# goodfet42jtag.net
KiCad netlist of a schematic drawn in EAGLE
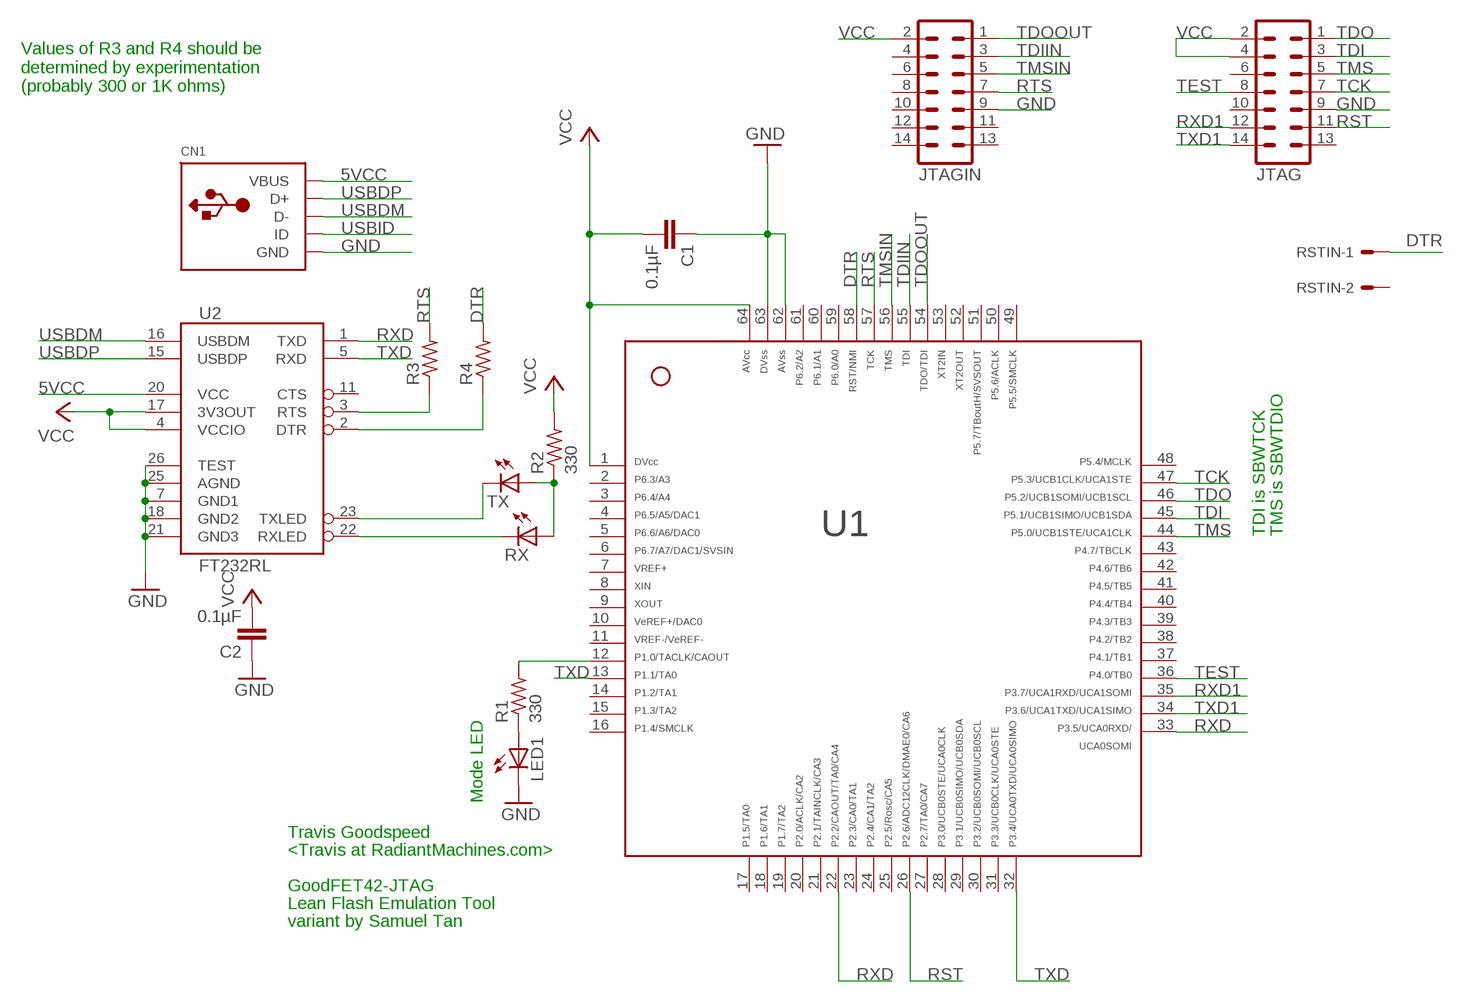
[diagram p0: schematic, sheet 1]

(export (version "E")
  (design (tool "Eeschema 10.0.6"))
  (components
    (comp (ref "C1")
      (value "0.1µF")
      (footprint "eagle-import:C0603")
      (libsource (lib "eagle-import") (part "C-EUC0603"))
    )
    (comp (ref "C2")
      (value "0.1µF")
      (footprint "eagle-import:C0603")
      (libsource (lib "eagle-import") (part "C-EUC0603"))
    )
    (comp (ref "CN1")
      (value "USBMINIB")
      (footprint "eagle-import:USB-MINIB")
      (libsource (lib "eagle-import") (part "USBMINIB"))
    )
    (comp (ref "JTAG")
      (value "MA07-2")
      (footprint "eagle-import:MA07-2")
      (libsource (lib "eagle-import") (part "MA07-2"))
    )
    (comp (ref "JTAGIN")
      (value "MA07-2")
      (footprint "eagle-import:MA07-2")
      (libsource (lib "eagle-import") (part "MA07-2"))
    )
    (comp (ref "LED1")
      (value "LEDCHIP-LED0603")
      (footprint "eagle-import:CHIP-LED0603")
      (libsource (lib "eagle-import") (part "LEDCHIP-LED0603"))
    )
    (comp (ref "R1")
      (value "330")
      (footprint "eagle-import:R0603")
      (libsource (lib "eagle-import") (part "R-US_R0603"))
    )
    (comp (ref "R2")
      (value "330")
      (footprint "eagle-import:R0603")
      (libsource (lib "eagle-import") (part "R-US_R0603"))
    )
    (comp (ref "R3")
      (value "R-US_R0603")
      (footprint "eagle-import:R0603")
      (libsource (lib "eagle-import") (part "R-US_R0603"))
    )
    (comp (ref "R4")
      (value "R-US_R0603")
      (footprint "eagle-import:R0603")
      (libsource (lib "eagle-import") (part "R-US_R0603"))
    )
    (comp (ref "RSTIN")
      (value "332-02")
      (footprint "eagle-import:332-02")
      (libsource (lib "eagle-import") (part "332-02"))
    )
    (comp (ref "RX")
      (value "LEDCHIP-LED0603")
      (footprint "eagle-import:CHIP-LED0603")
      (libsource (lib "eagle-import") (part "LEDCHIP-LED0603"))
    )
    (comp (ref "TX")
      (value "LEDCHIP-LED0603")
      (footprint "eagle-import:CHIP-LED0603")
      (libsource (lib "eagle-import") (part "LEDCHIP-LED0603"))
    )
    (comp (ref "U1")
      (value "MSP430F2618TPM")
      (footprint "eagle-import:PM_PAG64")
      (libsource (lib "eagle-import") (part "F261X---PM64"))
    )
    (comp (ref "U2")
      (value "FT232RL")
      (footprint "eagle-import:SSOP28DB")
      (libsource (lib "eagle-import") (part "FT232RL-BASICSSOP"))
    )
  )
  (nets
    (net (code "1") (name "/5VCC") (class "Default")
      (node (ref "CN1") (pin "VBUS") (pinfunction "VBUS_VBUS") (pintype "power_in"))
      (node (ref "U2") (pin "20") (pinfunction "VCC_20") (pintype "power_in"))
    )
    (net (code "2") (name "/DTR") (class "Default")
      (node (ref "R4") (pin "2") (pinfunction "2_2") (pintype "passive"))
      (node (ref "RSTIN") (pin "1") (pinfunction "S_1") (pintype "passive"))
      (node (ref "U1") (pin "58") (pinfunction "58_58") (pintype "input"))
    )
    (net (code "3") (name "/RST") (class "Default")
      (node (ref "JTAG") (pin "11") (pinfunction "11_11") (pintype "passive"))
      (node (ref "U1") (pin "26") (pinfunction "26_26") (pintype "bidirectional"))
    )
    (net (code "4") (name "/RTS") (class "Default")
      (node (ref "JTAGIN") (pin "7") (pinfunction "7_7") (pintype "passive"))
      (node (ref "R3") (pin "2") (pinfunction "2_2") (pintype "passive"))
      (node (ref "U1") (pin "57") (pinfunction "57_57") (pintype "input"))
    )
    (net (code "5") (name "/RXD") (class "Default")
      (node (ref "U1") (pin "22") (pinfunction "22_22") (pintype "bidirectional"))
      (node (ref "U1") (pin "33") (pinfunction "33_33") (pintype "bidirectional"))
      (node (ref "U2") (pin "1") (pinfunction "TXD_1") (pintype "output"))
    )
    (net (code "6") (name "/RXD1") (class "Default")
      (node (ref "JTAG") (pin "12") (pinfunction "12_12") (pintype "passive"))
      (node (ref "U1") (pin "35") (pinfunction "35_35") (pintype "bidirectional"))
    )
    (net (code "7") (name "/TCK") (class "Default")
      (node (ref "JTAG") (pin "7") (pinfunction "7_7") (pintype "passive"))
      (node (ref "U1") (pin "47") (pinfunction "47_47") (pintype "bidirectional"))
    )
    (net (code "8") (name "/TDI") (class "Default")
      (node (ref "JTAG") (pin "3") (pinfunction "3_3") (pintype "passive"))
      (node (ref "U1") (pin "45") (pinfunction "45_45") (pintype "bidirectional"))
    )
    (net (code "9") (name "/TDIIN") (class "Default")
      (node (ref "JTAGIN") (pin "3") (pinfunction "3_3") (pintype "passive"))
      (node (ref "U1") (pin "55") (pinfunction "55_55") (pintype "input"))
    )
    (net (code "10") (name "/TDO") (class "Default")
      (node (ref "JTAG") (pin "1") (pinfunction "1_1") (pintype "passive"))
      (node (ref "U1") (pin "46") (pinfunction "46_46") (pintype "bidirectional"))
    )
    (net (code "11") (name "/TDOOUT") (class "Default")
      (node (ref "JTAGIN") (pin "1") (pinfunction "1_1") (pintype "passive"))
      (node (ref "U1") (pin "54") (pinfunction "54_54") (pintype "bidirectional"))
    )
    (net (code "12") (name "/TEST") (class "Default")
      (node (ref "JTAG") (pin "8") (pinfunction "8_8") (pintype "passive"))
      (node (ref "U1") (pin "36") (pinfunction "36_36") (pintype "output"))
    )
    (net (code "13") (name "/TMS") (class "Default")
      (node (ref "JTAG") (pin "5") (pinfunction "5_5") (pintype "passive"))
      (node (ref "U1") (pin "44") (pinfunction "44_44") (pintype "bidirectional"))
    )
    (net (code "14") (name "/TMSIN") (class "Default")
      (node (ref "JTAGIN") (pin "5") (pinfunction "5_5") (pintype "passive"))
      (node (ref "U1") (pin "56") (pinfunction "56_56") (pintype "input"))
    )
    (net (code "15") (name "/TXD") (class "Default")
      (node (ref "U1") (pin "13") (pinfunction "13_13") (pintype "bidirectional"))
      (node (ref "U1") (pin "32") (pinfunction "32_32") (pintype "bidirectional"))
      (node (ref "U2") (pin "5") (pinfunction "RXD_5") (pintype "input"))
    )
    (net (code "16") (name "/TXD1") (class "Default")
      (node (ref "JTAG") (pin "14") (pinfunction "14_14") (pintype "passive"))
      (node (ref "U1") (pin "34") (pinfunction "34_34") (pintype "bidirectional"))
    )
    (net (code "17") (name "/USBDM") (class "Default")
      (node (ref "CN1") (pin "D-") (pinfunction "D-_D-") (pintype "bidirectional"))
      (node (ref "U2") (pin "16") (pinfunction "USBDM_16") (pintype "bidirectional"))
    )
    (net (code "18") (name "/USBDP") (class "Default")
      (node (ref "CN1") (pin "D+") (pinfunction "D+_D+") (pintype "bidirectional"))
      (node (ref "U2") (pin "15") (pinfunction "USBDP_15") (pintype "bidirectional"))
    )
    (net (code "19") (name "/USBID") (class "Default")
      (node (ref "CN1") (pin "ID") (pinfunction "ID_ID") (pintype "bidirectional"))
    )
    (net (code "20") (name "GND") (class "Default")
      (node (ref "C1") (pin "1") (pinfunction "1_1") (pintype "passive"))
      (node (ref "C2") (pin "1") (pinfunction "1_1") (pintype "passive"))
      (node (ref "CN1") (pin "GND") (pinfunction "GND_GND") (pintype "power_in"))
      (node (ref "JTAG") (pin "9") (pinfunction "9_9") (pintype "passive"))
      (node (ref "JTAGIN") (pin "9") (pinfunction "9_9") (pintype "passive"))
      (node (ref "LED1") (pin "C") (pinfunction "C_C") (pintype "passive"))
      (node (ref "U1") (pin "62") (pinfunction "62_62") (pintype "power_in"))
      (node (ref "U1") (pin "63") (pinfunction "63_63") (pintype "power_in"))
      (node (ref "U2") (pin "18") (pinfunction "GND2_18") (pintype "power_in"))
      (node (ref "U2") (pin "21") (pinfunction "GND3_21") (pintype "power_in"))
      (node (ref "U2") (pin "25") (pinfunction "AGND_25") (pintype "power_in"))
      (node (ref "U2") (pin "26") (pinfunction "TEST_26") (pintype "input"))
      (node (ref "U2") (pin "7") (pinfunction "GND1_7") (pintype "power_in"))
    )
    (net (code "21") (name "Net-(LED1-PadA)") (class "Default")
      (node (ref "LED1") (pin "A") (pinfunction "A_A") (pintype "passive"))
      (node (ref "R1") (pin "1") (pinfunction "1_1") (pintype "passive"))
    )
    (net (code "22") (name "Net-(R1-Pad2)") (class "Default")
      (node (ref "R1") (pin "2") (pinfunction "2_2") (pintype "passive"))
      (node (ref "U1") (pin "12") (pinfunction "12_12") (pintype "bidirectional"))
    )
    (net (code "23") (name "Net-(R2-Pad1)") (class "Default")
      (node (ref "R2") (pin "1") (pinfunction "1_1") (pintype "passive"))
      (node (ref "RX") (pin "A") (pinfunction "A_A") (pintype "passive"))
      (node (ref "TX") (pin "A") (pinfunction "A_A") (pintype "passive"))
    )
    (net (code "24") (name "Net-(U2-DTR)") (class "Default")
      (node (ref "R4") (pin "1") (pinfunction "1_1") (pintype "passive"))
      (node (ref "U2") (pin "2") (pinfunction "DTR_2") (pintype "bidirectional"))
    )
    (net (code "25") (name "Net-(U2-RTS)") (class "Default")
      (node (ref "R3") (pin "1") (pinfunction "1_1") (pintype "passive"))
      (node (ref "U2") (pin "3") (pinfunction "RTS_3") (pintype "bidirectional"))
    )
    (net (code "26") (name "Net-(U2-RXLED)") (class "Default")
      (node (ref "RX") (pin "C") (pinfunction "C_C") (pintype "passive"))
      (node (ref "U2") (pin "22") (pinfunction "RXLED_22") (pintype "bidirectional"))
    )
    (net (code "27") (name "Net-(U2-TXLED)") (class "Default")
      (node (ref "TX") (pin "C") (pinfunction "C_C") (pintype "passive"))
      (node (ref "U2") (pin "23") (pinfunction "TXLED_23") (pintype "bidirectional"))
    )
    (net (code "28") (name "VCC") (class "Default")
      (node (ref "C1") (pin "2") (pinfunction "2_2") (pintype "passive"))
      (node (ref "C2") (pin "2") (pinfunction "2_2") (pintype "passive"))
      (node (ref "JTAG") (pin "2") (pinfunction "2_2") (pintype "passive"))
      (node (ref "JTAG") (pin "4") (pinfunction "4_4") (pintype "passive"))
      (node (ref "JTAGIN") (pin "2") (pinfunction "2_2") (pintype "passive"))
      (node (ref "R2") (pin "2") (pinfunction "2_2") (pintype "passive"))
      (node (ref "U1") (pin "1") (pinfunction "1_1") (pintype "power_in"))
      (node (ref "U1") (pin "64") (pinfunction "64_64") (pintype "power_in"))
      (node (ref "U2") (pin "17") (pinfunction "3V3OUT_17") (pintype "output"))
      (node (ref "U2") (pin "4") (pinfunction "VCCIO_4") (pintype "power_in"))
    )
    (net (code "29") (name "unconnected-(JTAG-Pad6)") (class "Default")
      (node (ref "JTAG") (pin "6") (pinfunction "6_6") (pintype "passive"))
    )
    (net (code "30") (name "unconnected-(JTAG-Pad10)") (class "Default")
      (node (ref "JTAG") (pin "10") (pinfunction "10_10") (pintype "passive"))
    )
    (net (code "31") (name "unconnected-(JTAG-Pad13)") (class "Default")
      (node (ref "JTAG") (pin "13") (pinfunction "13_13") (pintype "passive"))
    )
    (net (code "32") (name "unconnected-(JTAGIN-Pad4)") (class "Default")
      (node (ref "JTAGIN") (pin "4") (pinfunction "4_4") (pintype "passive"))
    )
    (net (code "33") (name "unconnected-(JTAGIN-Pad6)") (class "Default")
      (node (ref "JTAGIN") (pin "6") (pinfunction "6_6") (pintype "passive"))
    )
    (net (code "34") (name "unconnected-(JTAGIN-Pad8)") (class "Default")
      (node (ref "JTAGIN") (pin "8") (pinfunction "8_8") (pintype "passive"))
    )
    (net (code "35") (name "unconnected-(JTAGIN-Pad10)") (class "Default")
      (node (ref "JTAGIN") (pin "10") (pinfunction "10_10") (pintype "passive"))
    )
    (net (code "36") (name "unconnected-(JTAGIN-Pad11)") (class "Default")
      (node (ref "JTAGIN") (pin "11") (pinfunction "11_11") (pintype "passive"))
    )
    (net (code "37") (name "unconnected-(JTAGIN-Pad12)") (class "Default")
      (node (ref "JTAGIN") (pin "12") (pinfunction "12_12") (pintype "passive"))
    )
    (net (code "38") (name "unconnected-(JTAGIN-Pad13)") (class "Default")
      (node (ref "JTAGIN") (pin "13") (pinfunction "13_13") (pintype "passive"))
    )
    (net (code "39") (name "unconnected-(JTAGIN-Pad14)") (class "Default")
      (node (ref "JTAGIN") (pin "14") (pinfunction "14_14") (pintype "passive"))
    )
    (net (code "40") (name "unconnected-(RSTINB-S-Pad2)") (class "Default")
      (node (ref "RSTIN") (pin "2") (pinfunction "S_2") (pintype "passive"))
    )
    (net (code "41") (name "unconnected-(U1-Pad2)") (class "Default")
      (node (ref "U1") (pin "2") (pinfunction "2_2") (pintype "bidirectional"))
    )
    (net (code "42") (name "unconnected-(U1-Pad3)") (class "Default")
      (node (ref "U1") (pin "3") (pinfunction "3_3") (pintype "bidirectional"))
    )
    (net (code "43") (name "unconnected-(U1-Pad4)") (class "Default")
      (node (ref "U1") (pin "4") (pinfunction "4_4") (pintype "bidirectional"))
    )
    (net (code "44") (name "unconnected-(U1-Pad5)") (class "Default")
      (node (ref "U1") (pin "5") (pinfunction "5_5") (pintype "bidirectional"))
    )
    (net (code "45") (name "unconnected-(U1-Pad6)") (class "Default")
      (node (ref "U1") (pin "6") (pinfunction "6_6") (pintype "bidirectional"))
    )
    (net (code "46") (name "unconnected-(U1-Pad7)") (class "Default")
      (node (ref "U1") (pin "7") (pinfunction "7_7") (pintype "output"))
    )
    (net (code "47") (name "unconnected-(U1-Pad8)") (class "Default")
      (node (ref "U1") (pin "8") (pinfunction "8_8") (pintype "input"))
    )
    (net (code "48") (name "unconnected-(U1-Pad9)") (class "Default")
      (node (ref "U1") (pin "9") (pinfunction "9_9") (pintype "output"))
    )
    (net (code "49") (name "unconnected-(U1-Pad10)") (class "Default")
      (node (ref "U1") (pin "10") (pinfunction "10_10") (pintype "bidirectional"))
    )
    (net (code "50") (name "unconnected-(U1-Pad11)") (class "Default")
      (node (ref "U1") (pin "11") (pinfunction "11_11") (pintype "bidirectional"))
    )
    (net (code "51") (name "unconnected-(U1-Pad14)") (class "Default")
      (node (ref "U1") (pin "14") (pinfunction "14_14") (pintype "bidirectional"))
    )
    (net (code "52") (name "unconnected-(U1-Pad15)") (class "Default")
      (node (ref "U1") (pin "15") (pinfunction "15_15") (pintype "bidirectional"))
    )
    (net (code "53") (name "unconnected-(U1-Pad16)") (class "Default")
      (node (ref "U1") (pin "16") (pinfunction "16_16") (pintype "bidirectional"))
    )
    (net (code "54") (name "unconnected-(U1-Pad17)") (class "Default")
      (node (ref "U1") (pin "17") (pinfunction "17_17") (pintype "bidirectional"))
    )
    (net (code "55") (name "unconnected-(U1-Pad18)") (class "Default")
      (node (ref "U1") (pin "18") (pinfunction "18_18") (pintype "bidirectional"))
    )
    (net (code "56") (name "unconnected-(U1-Pad19)") (class "Default")
      (node (ref "U1") (pin "19") (pinfunction "19_19") (pintype "bidirectional"))
    )
    (net (code "57") (name "unconnected-(U1-Pad20)") (class "Default")
      (node (ref "U1") (pin "20") (pinfunction "20_20") (pintype "bidirectional"))
    )
    (net (code "58") (name "unconnected-(U1-Pad21)") (class "Default")
      (node (ref "U1") (pin "21") (pinfunction "21_21") (pintype "bidirectional"))
    )
    (net (code "59") (name "unconnected-(U1-Pad23)") (class "Default")
      (node (ref "U1") (pin "23") (pinfunction "23_23") (pintype "bidirectional"))
    )
    (net (code "60") (name "unconnected-(U1-Pad24)") (class "Default")
      (node (ref "U1") (pin "24") (pinfunction "24_24") (pintype "bidirectional"))
    )
    (net (code "61") (name "unconnected-(U1-Pad25)") (class "Default")
      (node (ref "U1") (pin "25") (pinfunction "25_25") (pintype "bidirectional"))
    )
    (net (code "62") (name "unconnected-(U1-Pad27)") (class "Default")
      (node (ref "U1") (pin "27") (pinfunction "27_27") (pintype "bidirectional"))
    )
    (net (code "63") (name "unconnected-(U1-Pad28)") (class "Default")
      (node (ref "U1") (pin "28") (pinfunction "28_28") (pintype "bidirectional"))
    )
    (net (code "64") (name "unconnected-(U1-Pad29)") (class "Default")
      (node (ref "U1") (pin "29") (pinfunction "29_29") (pintype "bidirectional"))
    )
    (net (code "65") (name "unconnected-(U1-Pad30)") (class "Default")
      (node (ref "U1") (pin "30") (pinfunction "30_30") (pintype "bidirectional"))
    )
    (net (code "66") (name "unconnected-(U1-Pad31)") (class "Default")
      (node (ref "U1") (pin "31") (pinfunction "31_31") (pintype "bidirectional"))
    )
    (net (code "67") (name "unconnected-(U1-Pad37)") (class "Default")
      (node (ref "U1") (pin "37") (pinfunction "37_37") (pintype "bidirectional"))
    )
    (net (code "68") (name "unconnected-(U1-Pad38)") (class "Default")
      (node (ref "U1") (pin "38") (pinfunction "38_38") (pintype "bidirectional"))
    )
    (net (code "69") (name "unconnected-(U1-Pad39)") (class "Default")
      (node (ref "U1") (pin "39") (pinfunction "39_39") (pintype "bidirectional"))
    )
    (net (code "70") (name "unconnected-(U1-Pad40)") (class "Default")
      (node (ref "U1") (pin "40") (pinfunction "40_40") (pintype "input"))
    )
    (net (code "71") (name "unconnected-(U1-Pad41)") (class "Default")
      (node (ref "U1") (pin "41") (pinfunction "41_41") (pintype "bidirectional"))
    )
    (net (code "72") (name "unconnected-(U1-Pad42)") (class "Default")
      (node (ref "U1") (pin "42") (pinfunction "42_42") (pintype "bidirectional"))
    )
    (net (code "73") (name "unconnected-(U1-Pad43)") (class "Default")
      (node (ref "U1") (pin "43") (pinfunction "43_43") (pintype "bidirectional"))
    )
    (net (code "74") (name "unconnected-(U1-Pad48)") (class "Default")
      (node (ref "U1") (pin "48") (pinfunction "48_48") (pintype "bidirectional"))
    )
    (net (code "75") (name "unconnected-(U1-Pad49)") (class "Default")
      (node (ref "U1") (pin "49") (pinfunction "49_49") (pintype "bidirectional"))
    )
    (net (code "76") (name "unconnected-(U1-Pad50)") (class "Default")
      (node (ref "U1") (pin "50") (pinfunction "50_50") (pintype "bidirectional"))
    )
    (net (code "77") (name "unconnected-(U1-Pad51)") (class "Default")
      (node (ref "U1") (pin "51") (pinfunction "51_51") (pintype "bidirectional"))
    )
    (net (code "78") (name "unconnected-(U1-Pad52)") (class "Default")
      (node (ref "U1") (pin "52") (pinfunction "52_52") (pintype "output"))
    )
    (net (code "79") (name "unconnected-(U1-Pad53)") (class "Default")
      (node (ref "U1") (pin "53") (pinfunction "53_53") (pintype "input"))
    )
    (net (code "80") (name "unconnected-(U1-Pad59)") (class "Default")
      (node (ref "U1") (pin "59") (pinfunction "59_59") (pintype "bidirectional"))
    )
    (net (code "81") (name "unconnected-(U1-Pad60)") (class "Default")
      (node (ref "U1") (pin "60") (pinfunction "60_60") (pintype "bidirectional"))
    )
    (net (code "82") (name "unconnected-(U1-Pad61)") (class "Default")
      (node (ref "U1") (pin "61") (pinfunction "61_61") (pintype "bidirectional"))
    )
    (net (code "83") (name "unconnected-(U2-CTS-Pad11)") (class "Default")
      (node (ref "U2") (pin "11") (pinfunction "CTS_11") (pintype "bidirectional"))
    )
  )
)
